# HIGH-IP3-PGA103.net
KiCad netlist of a schematic drawn in EAGLE
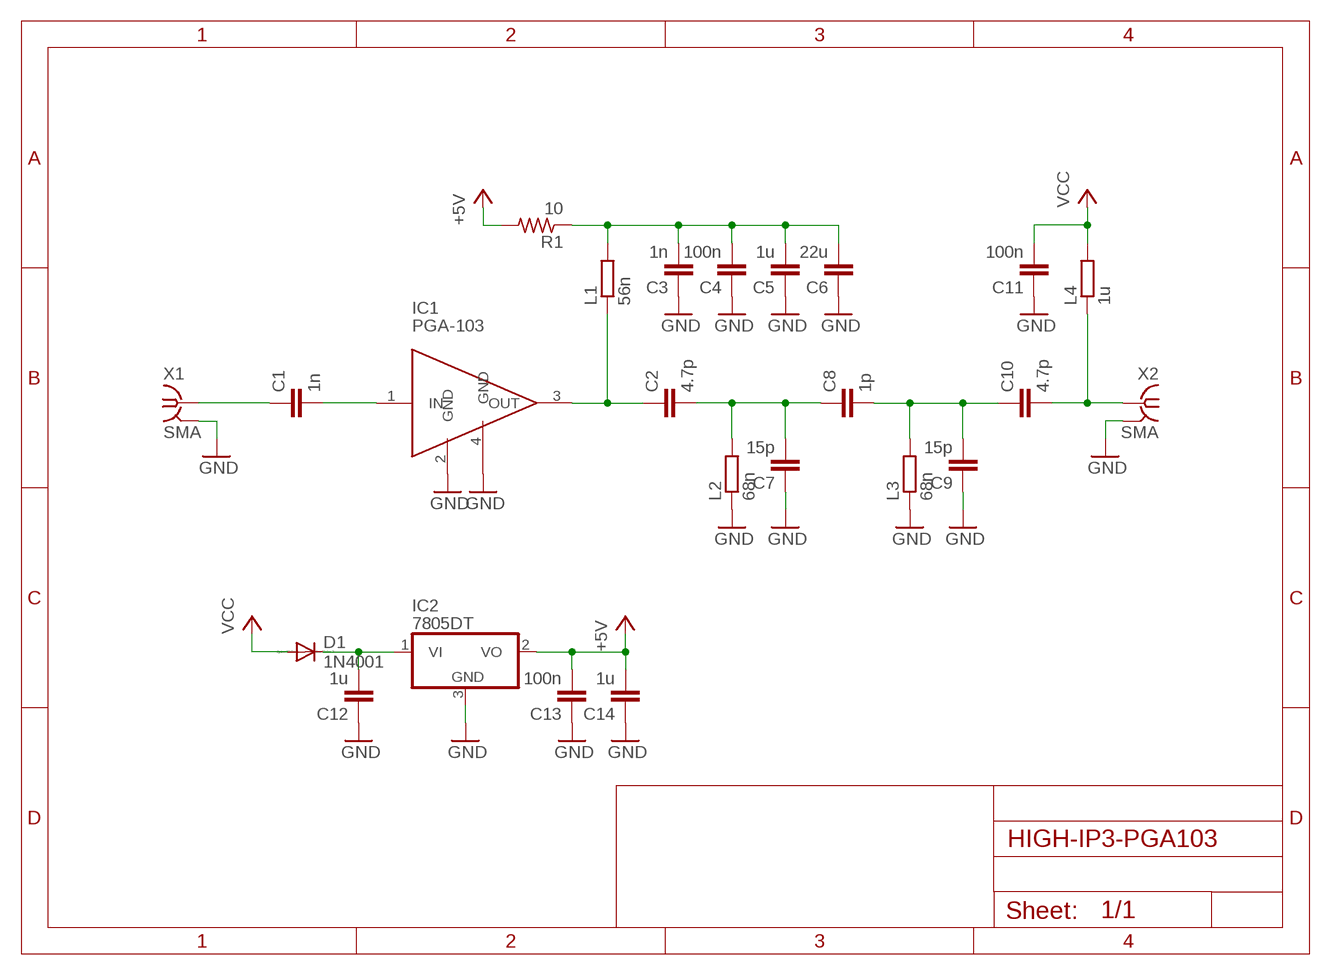
[diagram p0: schematic, sheet 1]

(export (version "E")
  (design (tool "Eeschema 10.0.6"))
  (components
    (comp (ref "C1")
      (value "1n")
      (footprint "eagle-import:C0805")
      (libsource (lib "eagle-import") (part "C-EUC0805"))
    )
    (comp (ref "C2")
      (value "4.7p")
      (footprint "eagle-import:C0805")
      (libsource (lib "eagle-import") (part "C-EUC0805"))
    )
    (comp (ref "C3")
      (value "1n")
      (footprint "eagle-import:C0805")
      (libsource (lib "eagle-import") (part "C-EUC0805"))
    )
    (comp (ref "C4")
      (value "100n")
      (footprint "eagle-import:C0805")
      (libsource (lib "eagle-import") (part "C-EUC0805"))
    )
    (comp (ref "C5")
      (value "1u")
      (footprint "eagle-import:C0805")
      (libsource (lib "eagle-import") (part "C-EUC0805"))
    )
    (comp (ref "C6")
      (value "22u")
      (footprint "eagle-import:C0805")
      (libsource (lib "eagle-import") (part "C-EUC0805"))
    )
    (comp (ref "C7")
      (value "15p")
      (footprint "eagle-import:C0805")
      (libsource (lib "eagle-import") (part "C-EUC0805"))
    )
    (comp (ref "C8")
      (value "1p")
      (footprint "eagle-import:C0805")
      (libsource (lib "eagle-import") (part "C-EUC0805"))
    )
    (comp (ref "C9")
      (value "15p")
      (footprint "eagle-import:C0805")
      (libsource (lib "eagle-import") (part "C-EUC0805"))
    )
    (comp (ref "C10")
      (value "4.7p")
      (footprint "eagle-import:C0805")
      (libsource (lib "eagle-import") (part "C-EUC0805"))
    )
    (comp (ref "C11")
      (value "100n")
      (footprint "eagle-import:C0805")
      (libsource (lib "eagle-import") (part "C-EUC0805"))
    )
    (comp (ref "C12")
      (value "1u")
      (footprint "eagle-import:C0805")
      (libsource (lib "eagle-import") (part "C-EUC0805"))
    )
    (comp (ref "C13")
      (value "100n")
      (footprint "eagle-import:C0805")
      (libsource (lib "eagle-import") (part "C-EUC0805"))
    )
    (comp (ref "C14")
      (value "1u")
      (footprint "eagle-import:C0805")
      (libsource (lib "eagle-import") (part "C-EUC0805"))
    )
    (comp (ref "D1")
      (value "1N4001")
      (footprint "eagle-import:DO35-7")
      (libsource (lib "eagle-import") (part "1N4148DO35-7"))
    )
    (comp (ref "IC1")
      (value "PGA-103")
      (footprint "eagle-import:SOT89")
      (libsource (lib "eagle-import") (part "PGA-103"))
    )
    (comp (ref "IC2")
      (value "7805DT")
      (footprint "eagle-import:TO252")
      (libsource (lib "eagle-import") (part "78DT05"))
    )
    (comp (ref "L1")
      (value "56n")
      (footprint "eagle-import:R0805")
      (libsource (lib "eagle-import") (part "R-EU_R0805"))
    )
    (comp (ref "L2")
      (value "68n")
      (footprint "eagle-import:R0805")
      (libsource (lib "eagle-import") (part "R-EU_R0805"))
    )
    (comp (ref "L3")
      (value "68n")
      (footprint "eagle-import:R0805")
      (libsource (lib "eagle-import") (part "R-EU_R0805"))
    )
    (comp (ref "L4")
      (value "1u")
      (footprint "eagle-import:R0805")
      (libsource (lib "eagle-import") (part "R-EU_R0805"))
    )
    (comp (ref "R1")
      (value "10")
      (footprint "eagle-import:R0805")
      (libsource (lib "eagle-import") (part "R-US_R0805"))
    )
    (comp (ref "X1")
      (value "SMA")
      (footprint "eagle-import:J502-ND-142-0701-801_806")
      (fields (field (name "MF") "JOHNSON COMPONENTS") (field (name "MPN") "142-0701-801"))
      (libsource (lib "eagle-import") (part "SMA-142-0701-801/806"))
    )
    (comp (ref "X2")
      (value "SMA")
      (footprint "eagle-import:J502-ND-142-0701-801_806")
      (fields (field (name "MF") "JOHNSON COMPONENTS") (field (name "MPN") "142-0701-801"))
      (libsource (lib "eagle-import") (part "SMA-142-0701-801/806"))
    )
  )
  (nets
    (net (code "1") (name "+5V") (class "Default")
      (node (ref "C13") (pin "2") (pinfunction "2_2") (pintype "passive"))
      (node (ref "C14") (pin "2") (pinfunction "2_2") (pintype "passive"))
      (node (ref "IC2") (pin "2") (pinfunction "VO_2") (pintype "passive"))
      (node (ref "R1") (pin "2") (pinfunction "2_2") (pintype "passive"))
    )
    (net (code "2") (name "GND") (class "Default")
      (node (ref "C11") (pin "1") (pinfunction "1_1") (pintype "passive"))
      (node (ref "C12") (pin "1") (pinfunction "1_1") (pintype "passive"))
      (node (ref "C13") (pin "1") (pinfunction "1_1") (pintype "passive"))
      (node (ref "C14") (pin "1") (pinfunction "1_1") (pintype "passive"))
      (node (ref "C3") (pin "1") (pinfunction "1_1") (pintype "passive"))
      (node (ref "C4") (pin "1") (pinfunction "1_1") (pintype "passive"))
      (node (ref "C5") (pin "1") (pinfunction "1_1") (pintype "passive"))
      (node (ref "C6") (pin "1") (pinfunction "1_1") (pintype "passive"))
      (node (ref "C7") (pin "1") (pinfunction "1_1") (pintype "passive"))
      (node (ref "C9") (pin "1") (pinfunction "1_1") (pintype "passive"))
      (node (ref "IC1") (pin "2") (pinfunction "GND_2") (pintype "power_in"))
      (node (ref "IC1") (pin "4") (pinfunction "GND_4") (pintype "power_in"))
      (node (ref "IC2") (pin "3") (pinfunction "GND_3") (pintype "passive"))
      (node (ref "L2") (pin "1") (pinfunction "1_1") (pintype "passive"))
      (node (ref "L3") (pin "1") (pinfunction "1_1") (pintype "passive"))
      (node (ref "X1") (pin "G@1") (pinfunction "2_G@1") (pintype "passive"))
      (node (ref "X1") (pin "G@2") (pinfunction "2_G@2") (pintype "passive"))
      (node (ref "X1") (pin "G@3") (pinfunction "2_G@3") (pintype "passive"))
      (node (ref "X1") (pin "G@4") (pinfunction "2_G@4") (pintype "passive"))
      (node (ref "X2") (pin "G@1") (pinfunction "2_G@1") (pintype "passive"))
      (node (ref "X2") (pin "G@2") (pinfunction "2_G@2") (pintype "passive"))
      (node (ref "X2") (pin "G@3") (pinfunction "2_G@3") (pintype "passive"))
      (node (ref "X2") (pin "G@4") (pinfunction "2_G@4") (pintype "passive"))
    )
    (net (code "3") (name "Net-(C1-Pad1)") (class "Default")
      (node (ref "C1") (pin "1") (pinfunction "1_1") (pintype "passive"))
      (node (ref "X1") (pin "1") (pinfunction "1_1") (pintype "passive"))
    )
    (net (code "4") (name "Net-(C2-Pad2)") (class "Default")
      (node (ref "C2") (pin "2") (pinfunction "2_2") (pintype "passive"))
      (node (ref "C7") (pin "2") (pinfunction "2_2") (pintype "passive"))
      (node (ref "C8") (pin "1") (pinfunction "1_1") (pintype "passive"))
      (node (ref "L2") (pin "2") (pinfunction "2_2") (pintype "passive"))
    )
    (net (code "5") (name "Net-(C3-Pad2)") (class "Default")
      (node (ref "C3") (pin "2") (pinfunction "2_2") (pintype "passive"))
      (node (ref "C4") (pin "2") (pinfunction "2_2") (pintype "passive"))
      (node (ref "C5") (pin "2") (pinfunction "2_2") (pintype "passive"))
      (node (ref "C6") (pin "2") (pinfunction "2_2") (pintype "passive"))
      (node (ref "L1") (pin "2") (pinfunction "2_2") (pintype "passive"))
      (node (ref "R1") (pin "1") (pinfunction "1_1") (pintype "passive"))
    )
    (net (code "6") (name "Net-(C10-Pad1)") (class "Default")
      (node (ref "C10") (pin "1") (pinfunction "1_1") (pintype "passive"))
      (node (ref "C8") (pin "2") (pinfunction "2_2") (pintype "passive"))
      (node (ref "C9") (pin "2") (pinfunction "2_2") (pintype "passive"))
      (node (ref "L3") (pin "2") (pinfunction "2_2") (pintype "passive"))
    )
    (net (code "7") (name "Net-(C10-Pad2)") (class "Default")
      (node (ref "C10") (pin "2") (pinfunction "2_2") (pintype "passive"))
      (node (ref "L4") (pin "1") (pinfunction "1_1") (pintype "passive"))
      (node (ref "X2") (pin "1") (pinfunction "1_1") (pintype "passive"))
    )
    (net (code "8") (name "Net-(IC1-IN)") (class "Default")
      (node (ref "C1") (pin "2") (pinfunction "2_2") (pintype "passive"))
      (node (ref "IC1") (pin "1") (pinfunction "IN_1") (pintype "input"))
    )
    (net (code "9") (name "Net-(IC1-OUT)") (class "Default")
      (node (ref "C2") (pin "1") (pinfunction "1_1") (pintype "passive"))
      (node (ref "IC1") (pin "3") (pinfunction "OUT_3") (pintype "output"))
      (node (ref "L1") (pin "1") (pinfunction "1_1") (pintype "passive"))
    )
    (net (code "10") (name "Net-(IC2-VI)") (class "Default")
      (node (ref "C12") (pin "2") (pinfunction "2_2") (pintype "passive"))
      (node (ref "D1") (pin "C") (pinfunction "C_C") (pintype "passive"))
      (node (ref "IC2") (pin "1") (pinfunction "VI_1") (pintype "input"))
    )
    (net (code "11") (name "VCC") (class "Default")
      (node (ref "C11") (pin "2") (pinfunction "2_2") (pintype "passive"))
      (node (ref "D1") (pin "A") (pinfunction "A_A") (pintype "passive"))
      (node (ref "L4") (pin "2") (pinfunction "2_2") (pintype "passive"))
    )
  )
)
